# Lab_1.net
KiCad netlist of a schematic drawn in EAGLE
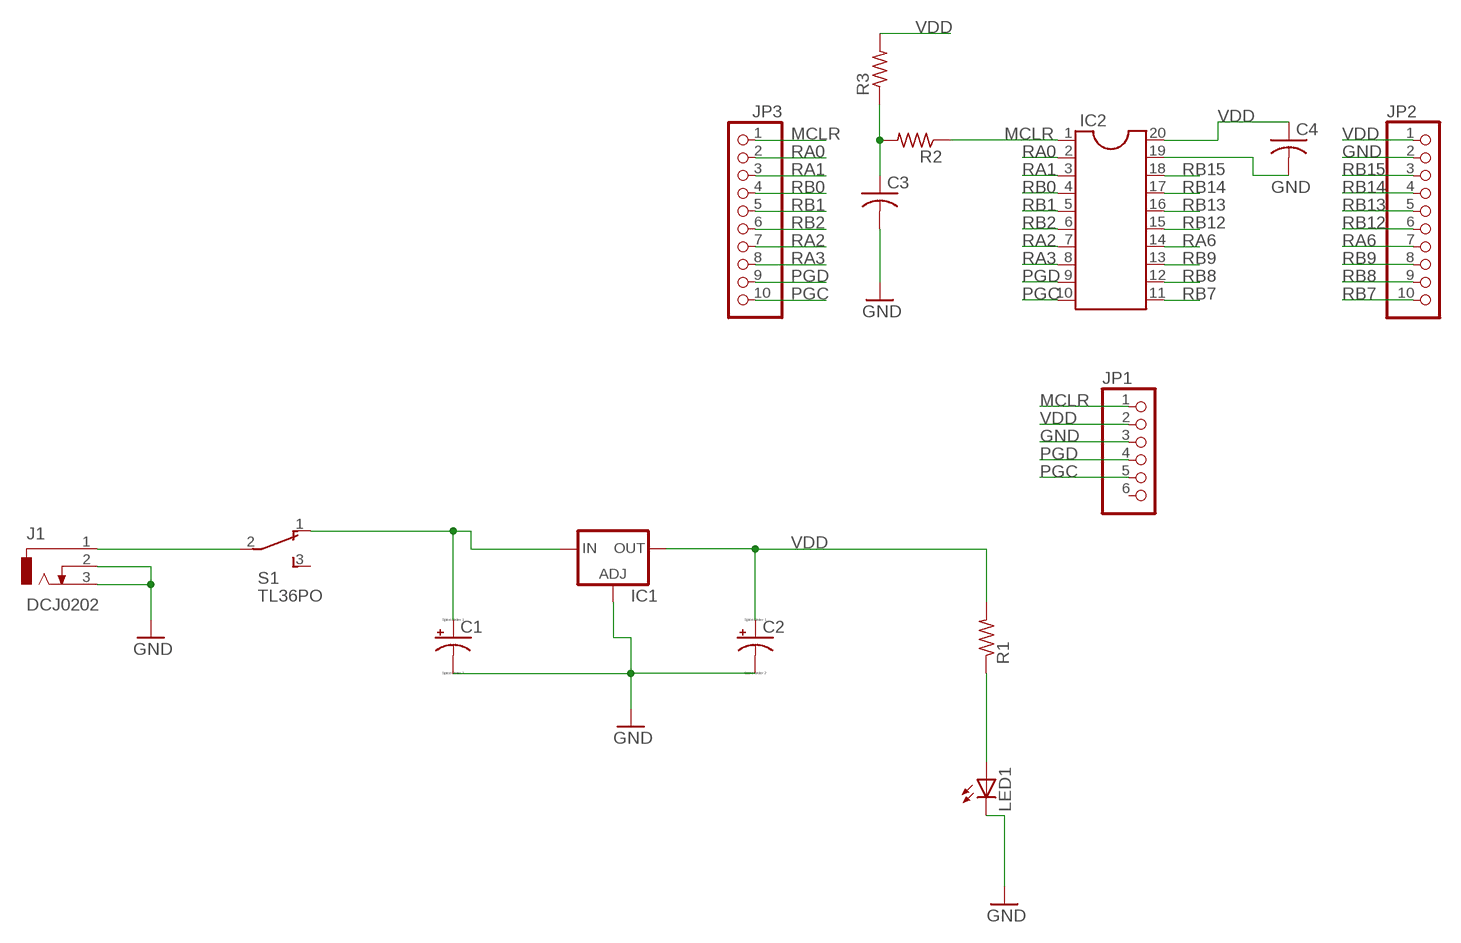
[diagram p0: schematic, sheet 1]

(export (version "E")
  (design (tool "Eeschema 10.0.6"))
  (components
    (comp (ref "C1")
      (value "CPOL-USE2.5-5")
      (footprint "eagle-import:E2,5-5")
      (libsource (lib "eagle-import") (part "CPOL-USE2.5-5"))
    )
    (comp (ref "C2")
      (value "CPOL-USE2.5-5")
      (footprint "eagle-import:E2,5-5")
      (libsource (lib "eagle-import") (part "CPOL-USE2.5-5"))
    )
    (comp (ref "C3")
      (value "C-US025-024X044")
      (footprint "eagle-import:C025-024X044")
      (libsource (lib "eagle-import") (part "C-US025-024X044"))
    )
    (comp (ref "C4")
      (value "C-US025-024X044")
      (footprint "eagle-import:C025-024X044")
      (libsource (lib "eagle-import") (part "C-US025-024X044"))
    )
    (comp (ref "IC1")
      (value "LM317TS")
      (footprint "eagle-import:317TS")
      (libsource (lib "eagle-import") (part "LM317TS"))
    )
    (comp (ref "IC2")
      (value "DIL20S")
      (footprint "eagle-import:SOCKET-20")
      (libsource (lib "eagle-import") (part "DIL20S"))
    )
    (comp (ref "J1")
      (value "DCJ0202")
      (footprint "eagle-import:DCJ0202")
      (libsource (lib "eagle-import") (part "DCJ0202"))
    )
    (comp (ref "JP1")
      (value "PINHD-1X6")
      (footprint "eagle-import:1X06")
      (libsource (lib "eagle-import") (part "PINHD-1X6"))
    )
    (comp (ref "JP2")
      (value "PINHD-1X10")
      (footprint "eagle-import:1X10")
      (libsource (lib "eagle-import") (part "PINHD-1X10"))
    )
    (comp (ref "JP3")
      (value "PINHD-1X10")
      (footprint "eagle-import:1X10")
      (libsource (lib "eagle-import") (part "PINHD-1X10"))
    )
    (comp (ref "LED1")
      (value "LED3MM")
      (footprint "eagle-import:LED3MM")
      (libsource (lib "eagle-import") (part "LED3MM"))
    )
    (comp (ref "R1")
      (value "R-US_0204/7")
      (footprint "eagle-import:0204_7")
      (libsource (lib "eagle-import") (part "R-US_0204/7"))
    )
    (comp (ref "R2")
      (value "R-US_0204/7")
      (footprint "eagle-import:0204_7")
      (libsource (lib "eagle-import") (part "R-US_0204/7"))
    )
    (comp (ref "R3")
      (value "R-US_0204/7")
      (footprint "eagle-import:0204_7")
      (libsource (lib "eagle-import") (part "R-US_0204/7"))
    )
    (comp (ref "S1")
      (value "TL36PO")
      (footprint "eagle-import:TL3XPO")
      (libsource (lib "eagle-import") (part "TL36PO"))
    )
  )
  (nets
    (net (code "1") (name "/MCLR") (class "Default")
      (node (ref "IC2") (pin "1") (pinfunction "1_1") (pintype "passive"))
      (node (ref "JP1") (pin "1") (pinfunction "1_1") (pintype "passive"))
      (node (ref "JP3") (pin "1") (pinfunction "1_1") (pintype "passive"))
      (node (ref "R2") (pin "1") (pinfunction "1_1") (pintype "passive"))
    )
    (net (code "2") (name "/PGC") (class "Default")
      (node (ref "IC2") (pin "10") (pinfunction "10_10") (pintype "passive"))
      (node (ref "JP1") (pin "5") (pinfunction "5_5") (pintype "passive"))
      (node (ref "JP3") (pin "10") (pinfunction "10_10") (pintype "passive"))
    )
    (net (code "3") (name "/PGD") (class "Default")
      (node (ref "IC2") (pin "9") (pinfunction "9_9") (pintype "passive"))
      (node (ref "JP1") (pin "4") (pinfunction "4_4") (pintype "passive"))
      (node (ref "JP3") (pin "9") (pinfunction "9_9") (pintype "passive"))
    )
    (net (code "4") (name "/RA0") (class "Default")
      (node (ref "IC2") (pin "2") (pinfunction "2_2") (pintype "passive"))
      (node (ref "JP3") (pin "2") (pinfunction "2_2") (pintype "passive"))
    )
    (net (code "5") (name "/RA1") (class "Default")
      (node (ref "IC2") (pin "3") (pinfunction "3_3") (pintype "passive"))
      (node (ref "JP3") (pin "3") (pinfunction "3_3") (pintype "passive"))
    )
    (net (code "6") (name "/RA2") (class "Default")
      (node (ref "IC2") (pin "7") (pinfunction "7_7") (pintype "passive"))
      (node (ref "JP3") (pin "7") (pinfunction "7_7") (pintype "passive"))
    )
    (net (code "7") (name "/RA3") (class "Default")
      (node (ref "IC2") (pin "8") (pinfunction "8_8") (pintype "passive"))
      (node (ref "JP3") (pin "8") (pinfunction "8_8") (pintype "passive"))
    )
    (net (code "8") (name "/RA6") (class "Default")
      (node (ref "IC2") (pin "14") (pinfunction "14_14") (pintype "passive"))
      (node (ref "JP2") (pin "7") (pinfunction "7_7") (pintype "passive"))
    )
    (net (code "9") (name "/RB0") (class "Default")
      (node (ref "IC2") (pin "4") (pinfunction "4_4") (pintype "passive"))
      (node (ref "JP3") (pin "4") (pinfunction "4_4") (pintype "passive"))
    )
    (net (code "10") (name "/RB1") (class "Default")
      (node (ref "IC2") (pin "5") (pinfunction "5_5") (pintype "passive"))
      (node (ref "JP3") (pin "5") (pinfunction "5_5") (pintype "passive"))
    )
    (net (code "11") (name "/RB2") (class "Default")
      (node (ref "IC2") (pin "6") (pinfunction "6_6") (pintype "passive"))
      (node (ref "JP3") (pin "6") (pinfunction "6_6") (pintype "passive"))
    )
    (net (code "12") (name "/RB7") (class "Default")
      (node (ref "IC2") (pin "11") (pinfunction "11_11") (pintype "passive"))
      (node (ref "JP2") (pin "10") (pinfunction "10_10") (pintype "passive"))
    )
    (net (code "13") (name "/RB8") (class "Default")
      (node (ref "IC2") (pin "12") (pinfunction "12_12") (pintype "passive"))
      (node (ref "JP2") (pin "9") (pinfunction "9_9") (pintype "passive"))
    )
    (net (code "14") (name "/RB9") (class "Default")
      (node (ref "IC2") (pin "13") (pinfunction "13_13") (pintype "passive"))
      (node (ref "JP2") (pin "8") (pinfunction "8_8") (pintype "passive"))
    )
    (net (code "15") (name "/RB12") (class "Default")
      (node (ref "IC2") (pin "15") (pinfunction "15_15") (pintype "passive"))
      (node (ref "JP2") (pin "6") (pinfunction "6_6") (pintype "passive"))
    )
    (net (code "16") (name "/RB13") (class "Default")
      (node (ref "IC2") (pin "16") (pinfunction "16_16") (pintype "passive"))
      (node (ref "JP2") (pin "5") (pinfunction "5_5") (pintype "passive"))
    )
    (net (code "17") (name "/RB14") (class "Default")
      (node (ref "IC2") (pin "17") (pinfunction "17_17") (pintype "passive"))
      (node (ref "JP2") (pin "4") (pinfunction "4_4") (pintype "passive"))
    )
    (net (code "18") (name "/RB15") (class "Default")
      (node (ref "IC2") (pin "18") (pinfunction "18_18") (pintype "passive"))
      (node (ref "JP2") (pin "3") (pinfunction "3_3") (pintype "passive"))
    )
    (net (code "19") (name "/VDD") (class "Default")
      (node (ref "C2") (pin "+") (pinfunction "+_+") (pintype "passive"))
      (node (ref "C4") (pin "1") (pinfunction "1_1") (pintype "passive"))
      (node (ref "IC1") (pin "2") (pinfunction "OUT_2") (pintype "passive"))
      (node (ref "IC2") (pin "20") (pinfunction "20_20") (pintype "passive"))
      (node (ref "JP1") (pin "2") (pinfunction "2_2") (pintype "passive"))
      (node (ref "JP2") (pin "1") (pinfunction "1_1") (pintype "passive"))
      (node (ref "R1") (pin "2") (pinfunction "2_2") (pintype "passive"))
      (node (ref "R3") (pin "2") (pinfunction "2_2") (pintype "passive"))
    )
    (net (code "20") (name "GND") (class "Default")
      (node (ref "C1") (pin "-") (pinfunction "-_-") (pintype "passive"))
      (node (ref "C2") (pin "-") (pinfunction "-_-") (pintype "passive"))
      (node (ref "C3") (pin "2") (pinfunction "2_2") (pintype "passive"))
      (node (ref "C4") (pin "2") (pinfunction "2_2") (pintype "passive"))
      (node (ref "IC1") (pin "1") (pinfunction "ADJ_1") (pintype "input"))
      (node (ref "IC2") (pin "19") (pinfunction "19_19") (pintype "passive"))
      (node (ref "J1") (pin "2") (pinfunction "2_2") (pintype "passive"))
      (node (ref "J1") (pin "3") (pinfunction "3_3") (pintype "passive"))
      (node (ref "JP1") (pin "3") (pinfunction "3_3") (pintype "passive"))
      (node (ref "JP2") (pin "2") (pinfunction "2_2") (pintype "passive"))
      (node (ref "LED1") (pin "K") (pinfunction "C_K") (pintype "passive"))
    )
    (net (code "21") (name "Net-(C3-Pad1)") (class "Default")
      (node (ref "C3") (pin "1") (pinfunction "1_1") (pintype "passive"))
      (node (ref "R2") (pin "2") (pinfunction "2_2") (pintype "passive"))
      (node (ref "R3") (pin "1") (pinfunction "1_1") (pintype "passive"))
    )
    (net (code "22") (name "Net-(IC1-IN)") (class "Default")
      (node (ref "C1") (pin "+") (pinfunction "+_+") (pintype "passive"))
      (node (ref "IC1") (pin "3") (pinfunction "IN_3") (pintype "input"))
      (node (ref "S1") (pin "1") (pinfunction "O_1") (pintype "passive"))
    )
    (net (code "23") (name "Net-(LED1-PadA)") (class "Default")
      (node (ref "LED1") (pin "A") (pinfunction "A_A") (pintype "passive"))
      (node (ref "R1") (pin "1") (pinfunction "1_1") (pintype "passive"))
    )
    (net (code "24") (name "Net-(S1-P)") (class "Default")
      (node (ref "J1") (pin "1") (pinfunction "1_1") (pintype "passive"))
      (node (ref "S1") (pin "2") (pinfunction "P_2") (pintype "passive"))
    )
    (net (code "25") (name "unconnected-(JP1-Pad6)") (class "Default")
      (node (ref "JP1") (pin "6") (pinfunction "6_6") (pintype "passive"))
    )
    (net (code "26") (name "unconnected-(S1-S-Pad3)") (class "Default")
      (node (ref "S1") (pin "3") (pinfunction "S_3") (pintype "passive"))
    )
  )
)
